# Camera.net
KiCad netlist of a schematic drawn in EAGLE
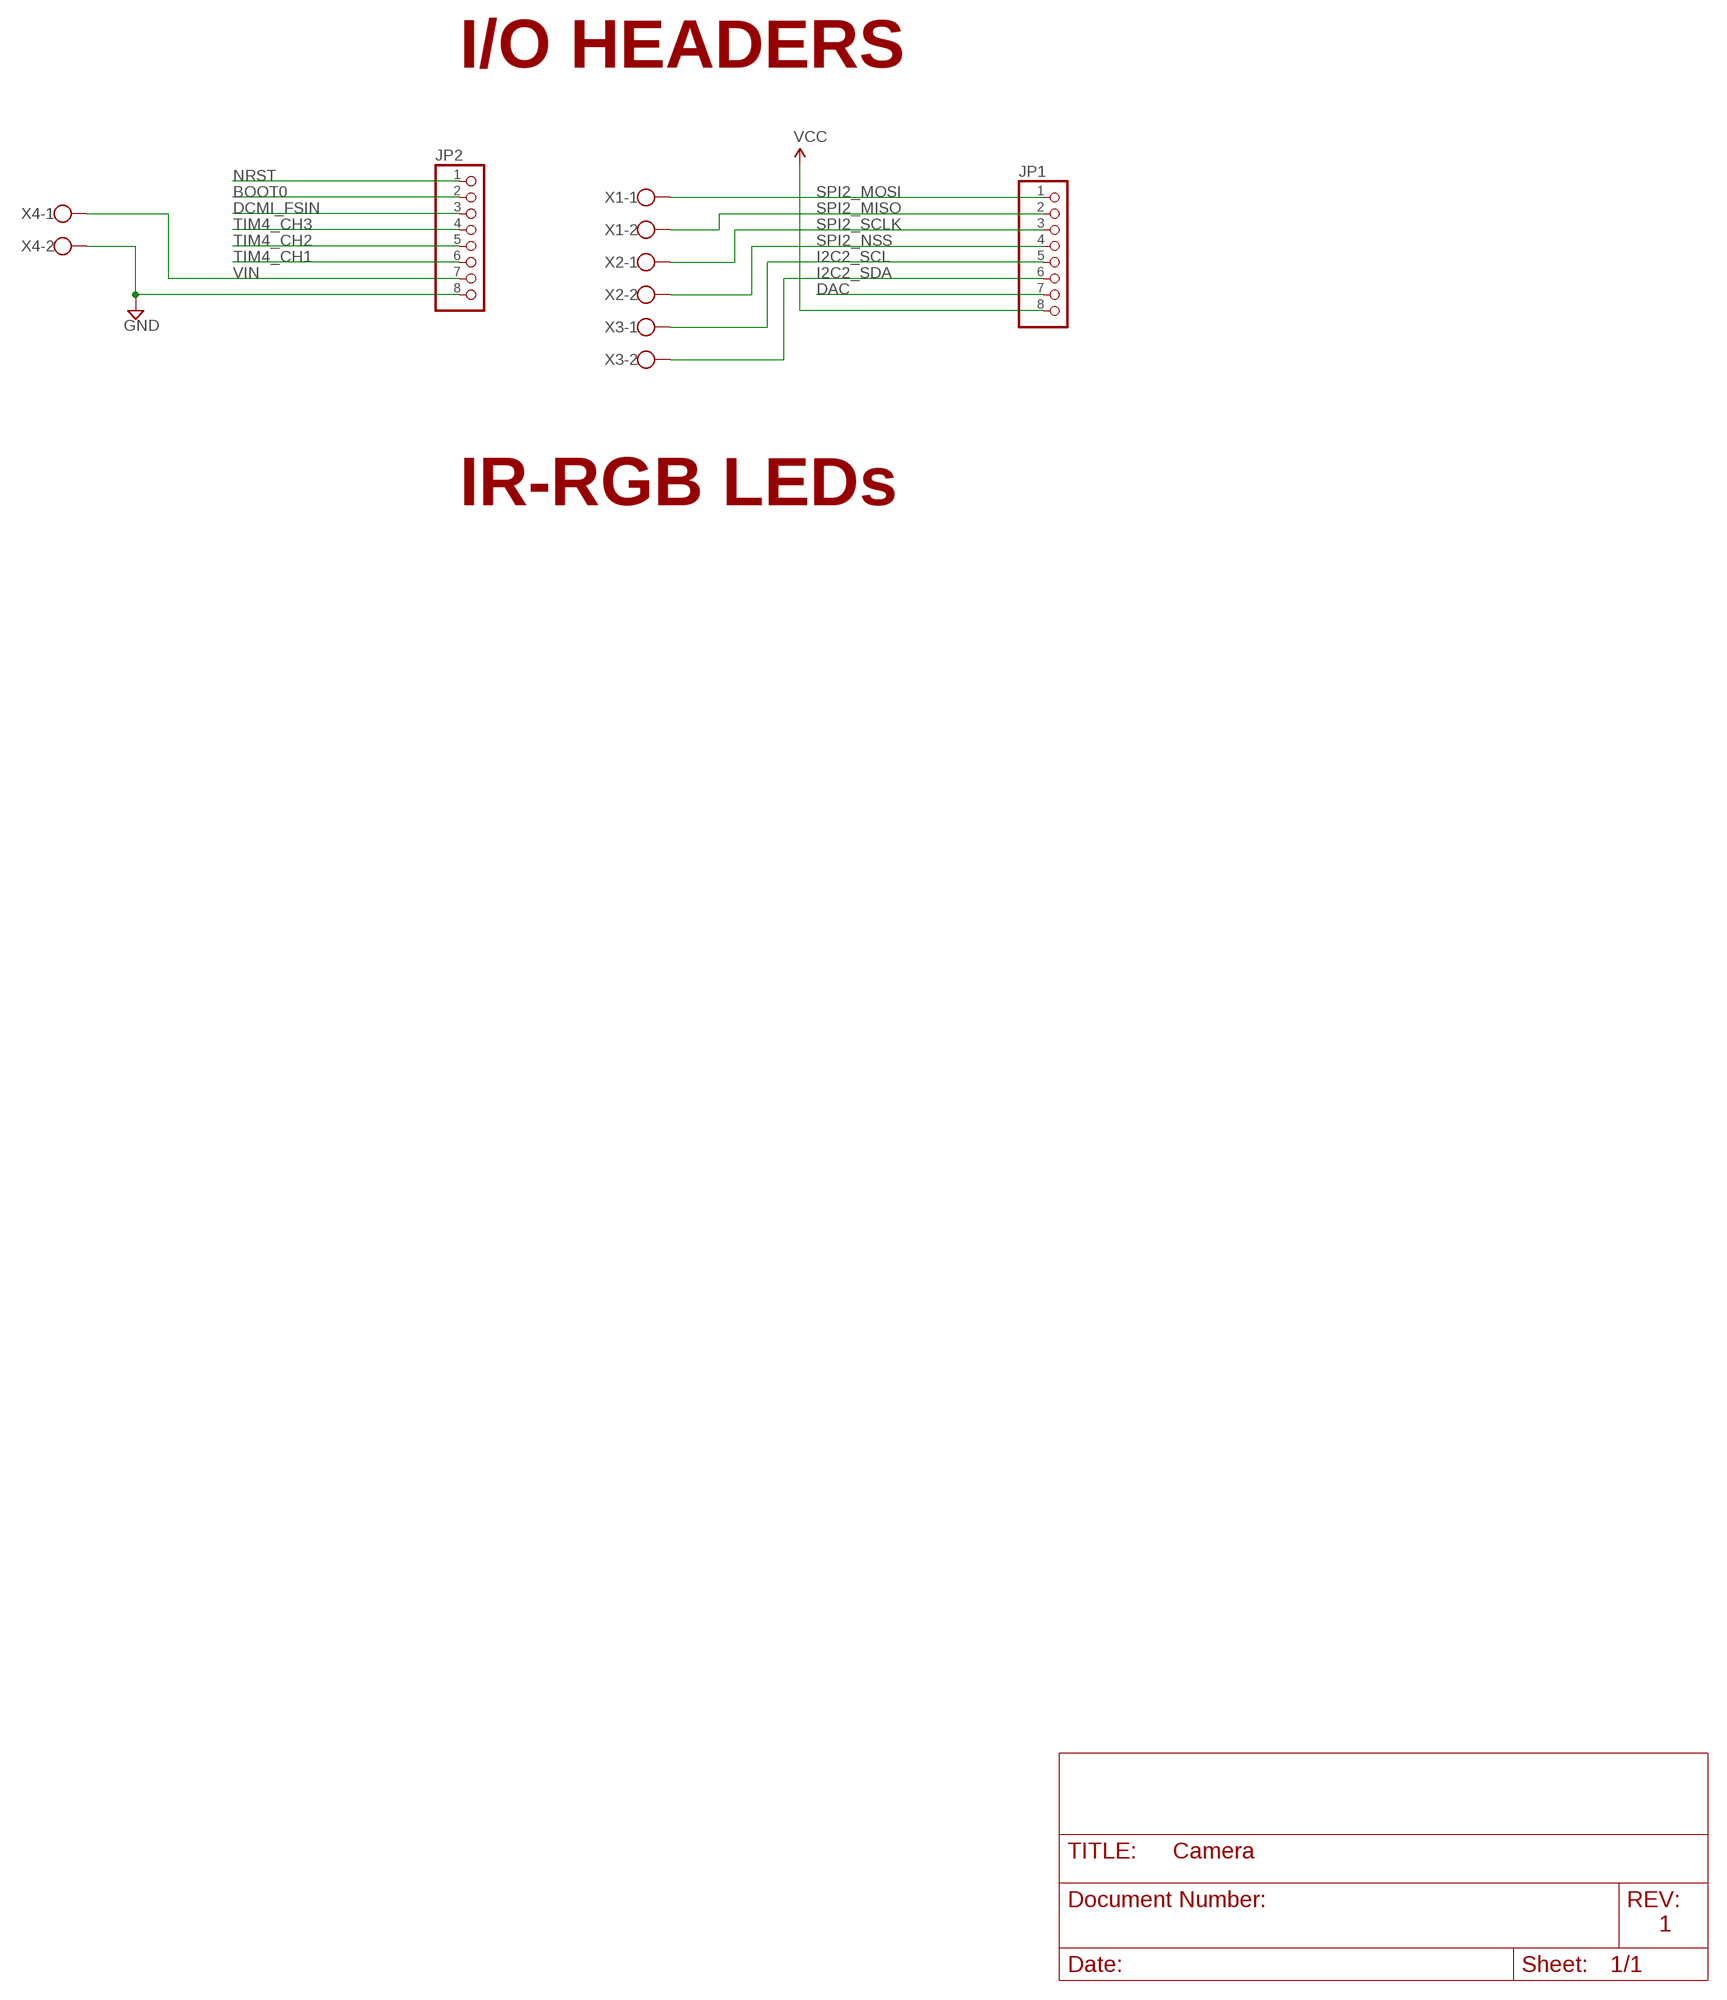
[diagram p0: schematic, sheet 1]

(export (version "E")
  (design (tool "Eeschema 10.0.6"))
  (components
    (comp (ref "JP1")
      (value "PINHD-1X8")
      (footprint "eagle-import:1X08")
      (libsource (lib "eagle-import") (part "PINHD-1X8"))
    )
    (comp (ref "JP2")
      (value "PINHD-1X8")
      (footprint "eagle-import:1X08")
      (libsource (lib "eagle-import") (part "PINHD-1X8"))
    )
    (comp (ref "X1")
      (value "W237-102")
      (footprint "eagle-import:W237-102")
      (fields (field (name "MPN") "237-102"))
      (libsource (lib "eagle-import") (part "W237-102"))
    )
    (comp (ref "X2")
      (value "W237-102")
      (footprint "eagle-import:W237-102")
      (fields (field (name "MPN") "237-102"))
      (libsource (lib "eagle-import") (part "W237-102"))
    )
    (comp (ref "X3")
      (value "W237-102")
      (footprint "eagle-import:W237-102")
      (fields (field (name "MPN") "237-102"))
      (libsource (lib "eagle-import") (part "W237-102"))
    )
    (comp (ref "X4")
      (value "W237-102")
      (footprint "eagle-import:W237-102")
      (fields (field (name "MPN") "237-102"))
      (libsource (lib "eagle-import") (part "W237-102"))
    )
  )
  (nets
    (net (code "1") (name "/BOOT0") (class "Default")
      (node (ref "JP2") (pin "2") (pinfunction "2_2") (pintype "passive"))
    )
    (net (code "2") (name "/DAC") (class "Default")
      (node (ref "JP1") (pin "7") (pinfunction "7_7") (pintype "passive"))
    )
    (net (code "3") (name "/DCMI_FSIN") (class "Default")
      (node (ref "JP2") (pin "3") (pinfunction "3_3") (pintype "passive"))
    )
    (net (code "4") (name "/I2C2_SCL") (class "Default")
      (node (ref "JP1") (pin "5") (pinfunction "5_5") (pintype "passive"))
      (node (ref "X3") (pin "1") (pinfunction "KL_1") (pintype "passive"))
    )
    (net (code "5") (name "/I2C2_SDA") (class "Default")
      (node (ref "JP1") (pin "6") (pinfunction "6_6") (pintype "passive"))
      (node (ref "X3") (pin "2") (pinfunction "KL_2") (pintype "passive"))
    )
    (net (code "6") (name "/NRST") (class "Default")
      (node (ref "JP2") (pin "1") (pinfunction "1_1") (pintype "passive"))
    )
    (net (code "7") (name "/SPI2_MISO") (class "Default")
      (node (ref "JP1") (pin "2") (pinfunction "2_2") (pintype "passive"))
      (node (ref "X1") (pin "2") (pinfunction "KL_2") (pintype "passive"))
    )
    (net (code "8") (name "/SPI2_MOSI") (class "Default")
      (node (ref "JP1") (pin "1") (pinfunction "1_1") (pintype "passive"))
      (node (ref "X1") (pin "1") (pinfunction "KL_1") (pintype "passive"))
    )
    (net (code "9") (name "/SPI2_NSS") (class "Default")
      (node (ref "JP1") (pin "4") (pinfunction "4_4") (pintype "passive"))
      (node (ref "X2") (pin "2") (pinfunction "KL_2") (pintype "passive"))
    )
    (net (code "10") (name "/SPI2_SCLK") (class "Default")
      (node (ref "JP1") (pin "3") (pinfunction "3_3") (pintype "passive"))
      (node (ref "X2") (pin "1") (pinfunction "KL_1") (pintype "passive"))
    )
    (net (code "11") (name "/TIM4_CH1") (class "Default")
      (node (ref "JP2") (pin "6") (pinfunction "6_6") (pintype "passive"))
    )
    (net (code "12") (name "/TIM4_CH2") (class "Default")
      (node (ref "JP2") (pin "5") (pinfunction "5_5") (pintype "passive"))
    )
    (net (code "13") (name "/TIM4_CH3") (class "Default")
      (node (ref "JP2") (pin "4") (pinfunction "4_4") (pintype "passive"))
    )
    (net (code "14") (name "/VIN") (class "Default")
      (node (ref "JP2") (pin "7") (pinfunction "7_7") (pintype "passive"))
      (node (ref "X4") (pin "1") (pinfunction "KL_1") (pintype "passive"))
    )
    (net (code "15") (name "GND") (class "Default")
      (node (ref "JP2") (pin "8") (pinfunction "8_8") (pintype "passive"))
      (node (ref "X4") (pin "2") (pinfunction "KL_2") (pintype "passive"))
    )
    (net (code "16") (name "VCC") (class "Default")
      (node (ref "JP1") (pin "8") (pinfunction "8_8") (pintype "passive"))
    )
  )
)
